# AST1025.net
KiCad netlist of a schematic drawn in EAGLE
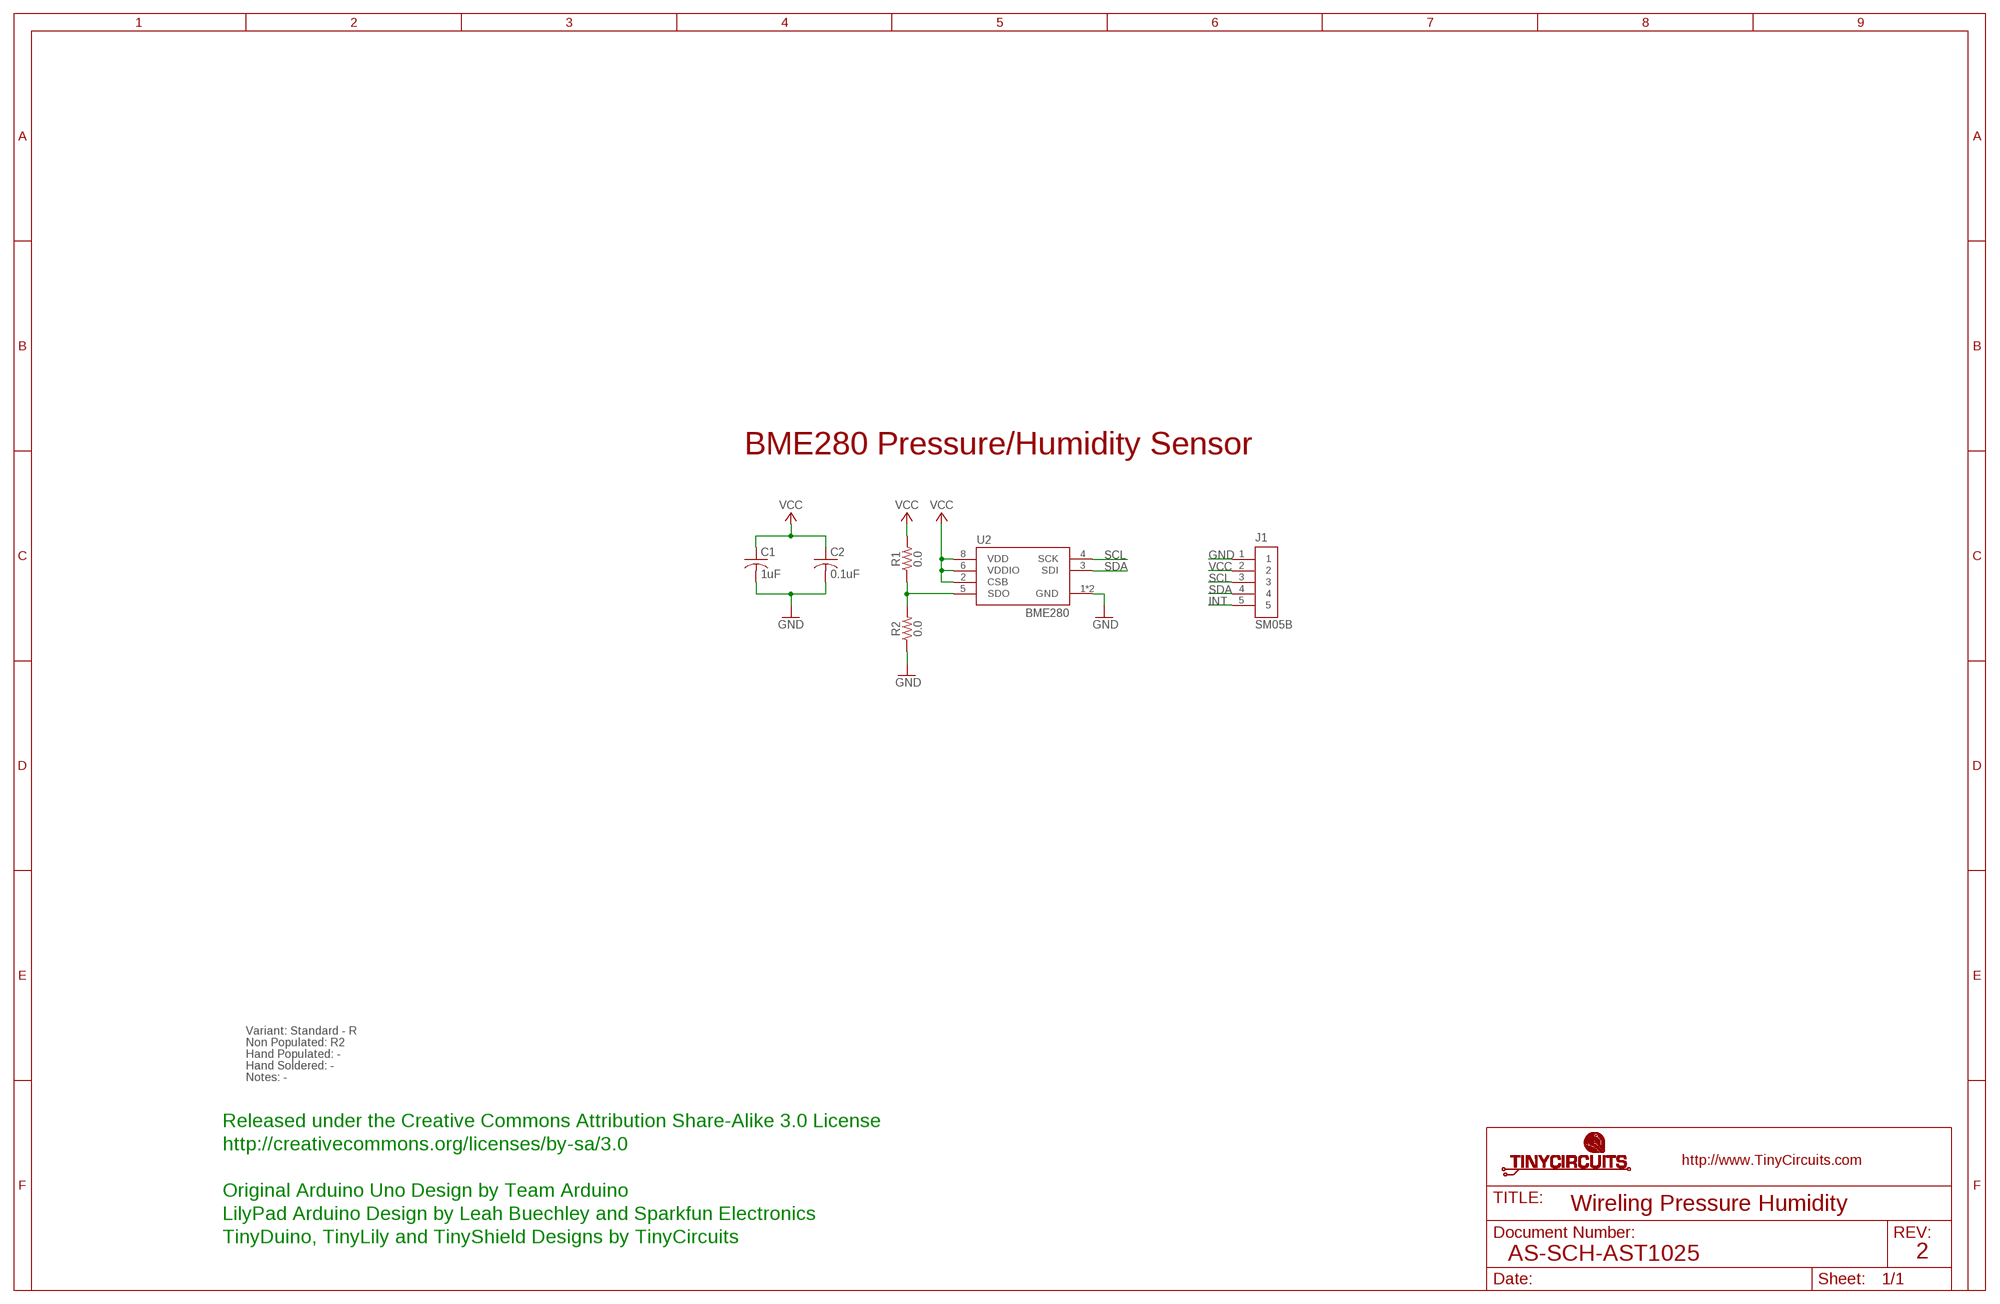
[diagram p0: schematic, sheet 1]

(export (version "E")
  (design (tool "Eeschema 10.0.6"))
  (components
    (comp (ref "C1")
      (value "1uF")
      (footprint "eagle-import:C0603")
      (fields (field (name "PARTNO") "AS-ITM-00410") (field (name "PARTNO_1") "AS-ITM-00410"))
      (libsource (lib "eagle-import") (part "AS-ITM-00410"))
    )
    (comp (ref "C2")
      (value "0.1uF")
      (footprint "eagle-import:C0402")
      (fields (field (name "PARTNO") "AS-ITM-00008"))
      (libsource (lib "eagle-import") (part "AS-ITM-00008"))
    )
    (comp (ref "J1")
      (value "SM05B")
      (footprint "eagle-import:JST_SH_5X1_EDGE")
      (fields (field (name "PARTNO") "AS-ITM-00340"))
      (libsource (lib "eagle-import") (part "AS-ITM-00340EDGE"))
    )
    (comp (ref "R1")
      (value "0.0")
      (footprint "eagle-import:0402")
      (fields (field (name "PARTNO") "AS-ITM-00076"))
      (libsource (lib "eagle-import") (part "AS-ITM-00076"))
    )
    (comp (ref "R2")
      (value "0.0")
      (footprint "eagle-import:0402")
      (fields (field (name "PARTNO") "AS-ITM-00076") (field (name "PARTNO_1") "AS-ITM-00076"))
      (libsource (lib "eagle-import") (part "AS-ITM-00076"))
    )
    (comp (ref "U2")
      (value "BME280")
      (footprint "eagle-import:BME280")
      (fields (field (name "PARTNO") "AS-ITM-00365"))
      (libsource (lib "eagle-import") (part "AS-ITM-00365"))
    )
  )
  (nets
    (net (code "1") (name "/INT") (class "Default")
      (node (ref "J1") (pin "5") (pinfunction "5_5") (pintype "bidirectional"))
    )
    (net (code "2") (name "/SCL") (class "Default")
      (node (ref "J1") (pin "3") (pinfunction "3_3") (pintype "bidirectional"))
      (node (ref "U2") (pin "4") (pinfunction "SCK_4") (pintype "bidirectional"))
    )
    (net (code "3") (name "/SDA") (class "Default")
      (node (ref "J1") (pin "4") (pinfunction "4_4") (pintype "bidirectional"))
      (node (ref "U2") (pin "3") (pinfunction "SDI_3") (pintype "bidirectional"))
    )
    (net (code "4") (name "GND") (class "Default")
      (node (ref "C1") (pin "2") (pinfunction "2_2") (pintype "passive"))
      (node (ref "C2") (pin "2") (pinfunction "2_2") (pintype "passive"))
      (node (ref "J1") (pin "1") (pinfunction "1_1") (pintype "bidirectional"))
      (node (ref "R2") (pin "1") (pinfunction "1_1") (pintype "passive"))
      (node (ref "U2") (pin "1") (pinfunction "GND_1") (pintype "bidirectional"))
      (node (ref "U2") (pin "7") (pinfunction "GND_7") (pintype "bidirectional"))
    )
    (net (code "5") (name "Net-(U2-SDO)") (class "Default")
      (node (ref "R1") (pin "1") (pinfunction "1_1") (pintype "passive"))
      (node (ref "R2") (pin "2") (pinfunction "2_2") (pintype "passive"))
      (node (ref "U2") (pin "5") (pinfunction "SDO_5") (pintype "bidirectional"))
    )
    (net (code "6") (name "VCC") (class "Default")
      (node (ref "C1") (pin "1") (pinfunction "1_1") (pintype "passive"))
      (node (ref "C2") (pin "1") (pinfunction "1_1") (pintype "passive"))
      (node (ref "J1") (pin "2") (pinfunction "2_2") (pintype "bidirectional"))
      (node (ref "R1") (pin "2") (pinfunction "2_2") (pintype "passive"))
      (node (ref "U2") (pin "2") (pinfunction "CSB_2") (pintype "bidirectional"))
      (node (ref "U2") (pin "6") (pinfunction "VDDIO_6") (pintype "bidirectional"))
      (node (ref "U2") (pin "8") (pinfunction "VDD_8") (pintype "bidirectional"))
    )
  )
)
